# CAN-Sheet.net
KiCad netlist of a schematic drawn in Altium Designer
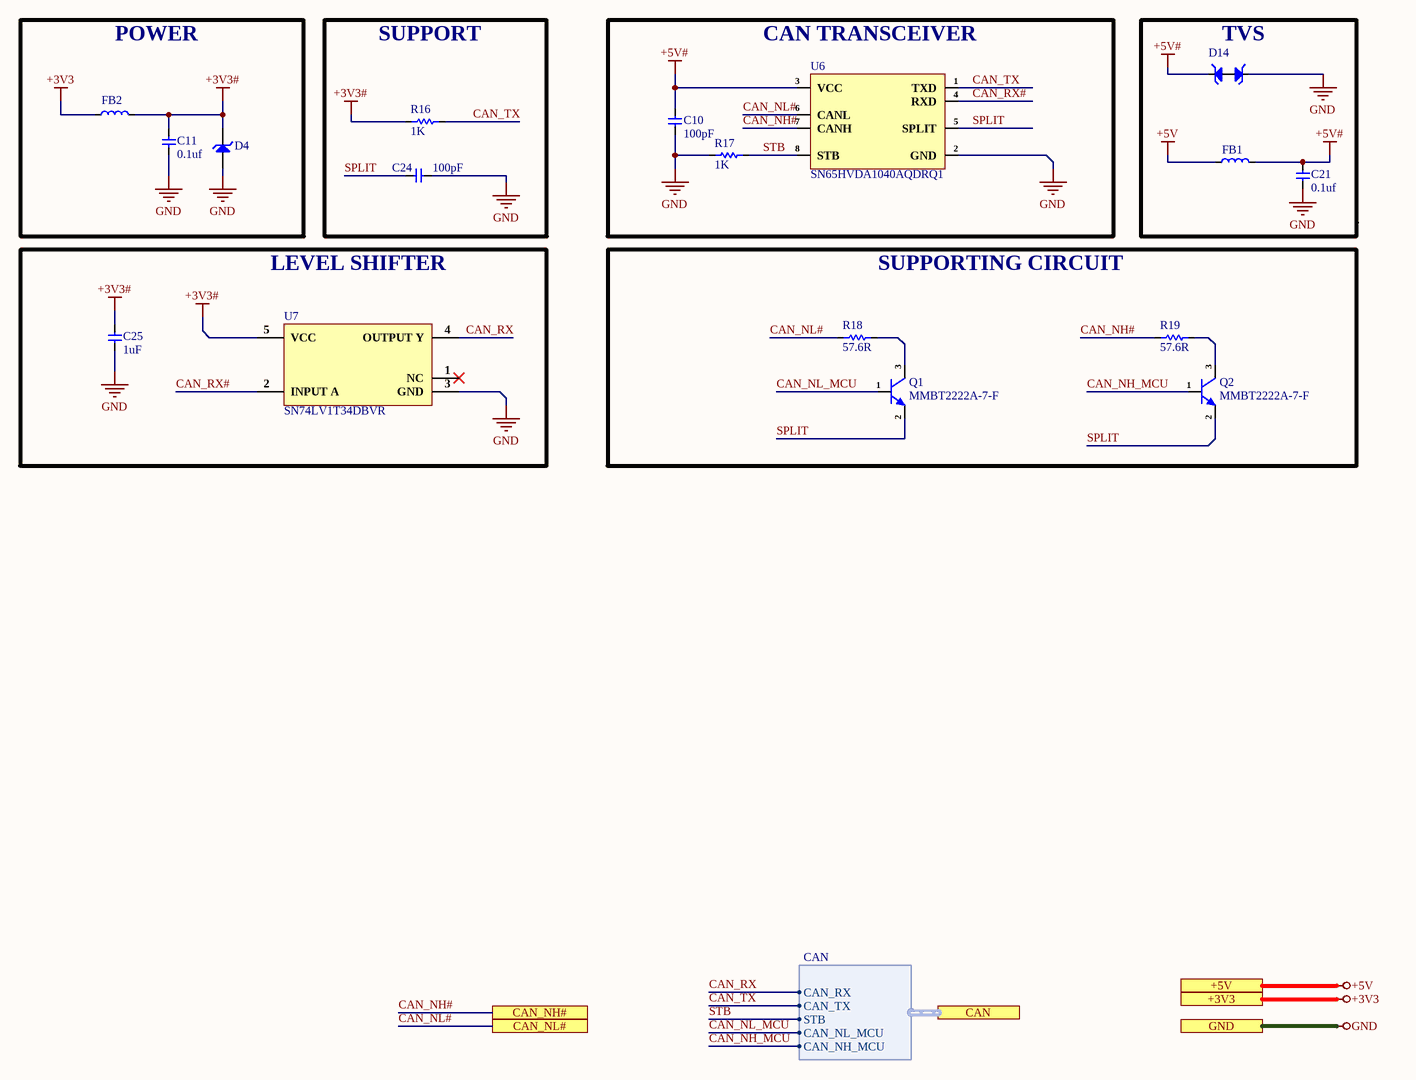
[diagram p0: CAN-Sheet.SchDoc]

(export (version "E")
  (design (tool "Eeschema 10.0.6"))
  (components
    (comp (ref "C10")
      (value "100pF")
      (footprint "Cap-0402")
      (description "CAP CER 100PF 50V C0G/NPO 0402")
      (fields
        (field (name "MANUFACTURER") "Yageo")
        (field (name "MANUFACTURER PART NUMBER") "CC0402JRNPO9BN101")
      )
      (libsource (lib "eSpark Libraries") (part "CC0402JRNPO9BN101"))
    )
    (comp (ref "C11")
      (value "0.1uf")
      (footprint "Cap-0402")
      (description "CAP CER 0.1UF 100V X5R 0402")
      (fields
        (field (name "MANUFACTURER") "Murata")
        (field (name "MANUFACTURER PART NUMBER") "GRM155R62A104KE14D")
      )
      (libsource (lib "eSpark Libraries") (part "GRM155R62A104KE14D"))
    )
    (comp (ref "C21")
      (value "0.1uf")
      (footprint "Cap-0402")
      (description "CAP CER 0.1UF 100V X5R 0402")
      (fields
        (field (name "MANUFACTURER") "Murata")
        (field (name "MANUFACTURER PART NUMBER") "GRM155R62A104KE14D")
      )
      (libsource (lib "eSpark Libraries") (part "GRM155R62A104KE14D"))
    )
    (comp (ref "C24")
      (value "100pF")
      (footprint "Cap-0402")
      (description "CAP CER 100PF 50V C0G/NPO 0402")
      (fields
        (field (name "MANUFACTURER") "Yageo")
        (field (name "MANUFACTURER PART NUMBER") "CC0402JRNPO9BN101")
      )
      (libsource (lib "eSpark Libraries") (part "CC0402JRNPO9BN101"))
    )
    (comp (ref "C25")
      (value "1uF")
      (footprint "Cap-0603")
      (description "CAP CER 1UF 25V X5R 0603")
      (fields
        (field (name "MANUFACTURER") "Yageo")
        (field (name "MANUFACTURER PART NUMBER") "CC0603KRX5R8BB105")
      )
      (libsource (lib "eSpark Libraries") (part "CC0603KRX5R8BB105"))
    )
    (comp (ref "D4")
      (value "AZ3003-01G")
      (footprint "SOD-123")
      (description "TVS SURGE PROTECTOR 1-CH 3.3V")
      (fields (field (name "MANUFACTURER") "Amazing"))
      (libsource (lib "eSpark Libraries") (part "AZ3003-01G"))
    )
    (comp (ref "D14")
      (value "PESD5V0H1BSFYL")
      (footprint "DSN0603-2")
      (description "TVS DIODE 5VWM 6.3VC DSN0603-2")
      (fields (field (name "MANUFACTURER") "Nexperia") (field (name "LCSC PART NUMBER") "C477989"))
      (libsource (lib "eSpark Libraries") (part "PESD5V0H1BSFYL"))
    )
    (comp (ref "FB1")
      (value "MPZ1608S121ATDH5")
      (footprint "IND-0603 (1608 Metric)")
      (description "FERRITE BEAD 120 OHM 0603 1LN")
      (fields (field (name "MANUFACTURER") "TDK") (field (name "TOLERANCE") "25%"))
      (libsource (lib "eSpark Libraries") (part "MPZ1608S121ATDH5"))
    )
    (comp (ref "FB2")
      (value "BLM15PG100SN1D")
      (footprint "IND-0402")
      (description "FERRITE BEAD 10 OHM 0402 1LN")
      (fields (field (name "MANUFACTURER") "Murata") (field (name "TOLERANCE") "25%"))
      (libsource (lib "eSpark Libraries") (part "BLM15PG100SN1D"))
    )
    (comp (ref "Q1")
      (value "MMBT2222A-7-F")
      (footprint "SOT-23")
      (description "TRANS NPN 40V 0.6A SMD SOT23-3")
      (fields (field (name "MANUFACTURER") "Diodes") (field (name "VOLTAGE") "40V"))
      (libsource (lib "eSpark Libraries") (part "MMBT2222A-7-F"))
    )
    (comp (ref "Q2")
      (value "MMBT2222A-7-F")
      (footprint "SOT-23")
      (description "TRANS NPN 40V 0.6A SMD SOT23-3")
      (fields (field (name "MANUFACTURER") "Diodes") (field (name "VOLTAGE") "40V"))
      (libsource (lib "eSpark Libraries") (part "MMBT2222A-7-F"))
    )
    (comp (ref "R16")
      (value "1K")
      (footprint "Res-0402")
      (description "RES 1K OHM 1% 1/16W 0402")
      (fields
        (field (name "MANUFACTURER") "Yageo")
        (field (name "MANUFACTURER PART NUMBER") "RC0402FR-071KL")
      )
      (libsource (lib "eSpark Libraries") (part "RC0402FR-071KL"))
    )
    (comp (ref "R17")
      (value "1K")
      (footprint "Res-0402")
      (description "RES SMD 1K OHM 1% 1/5W 0402")
      (fields
        (field (name "MANUFACTURER") "Vishay Dale")
        (field (name "MANUFACTURER PART NUMBER") "CRCW04021K00FKEDHP")
      )
      (libsource (lib "eSpark Libraries") (part "CRCW04021K00FKEDHP"))
    )
    (comp (ref "R18")
      (value "57.6R")
      (footprint "Res-0402")
      (description "RES SMD 57.6 OHM 1% 1/10W 0402")
      (fields
        (field (name "MANUFACTURER") "Panasonic")
        (field (name "MANUFACTURER PART NUMBER") "ERJ-2RKF57R6X")
      )
      (libsource (lib "eSpark Libraries") (part "ERJ-2RKF57R6X"))
    )
    (comp (ref "R19")
      (value "57.6R")
      (footprint "Res-0402")
      (description "RES SMD 57.6 OHM 1% 1/10W 0402")
      (fields
        (field (name "MANUFACTURER") "Panasonic")
        (field (name "MANUFACTURER PART NUMBER") "ERJ-2RKF57R6X")
      )
      (libsource (lib "eSpark Libraries") (part "ERJ-2RKF57R6X"))
    )
    (comp (ref "U6")
      (value "SN65HVDA1040AQDRQ1")
      (footprint "SOIC-8(0.154\", 3.90mm Width)")
      (description "IC TRANSCEIVER HALF 1/1 8SOIC")
      (fields (field (name "LCSC PART NUMBER") "C188675") (field (name "MANUFACTURER") "Texas Instruments"))
      (libsource (lib "eSpark Libraries") (part "SN65HVDA1040AQDRQ1"))
    )
    (comp (ref "U7")
      (value "SN74LV1T34DBVR")
      (footprint "SOT-23-5")
      (description "IC BUF NON-INVERT 5.5V SOT23-5")
      (fields (field (name "MANUFACTURER") "Texas Instruments") (field (name "LCSC PART NUMBER") "C100024"))
      (libsource (lib "eSpark Libraries") (part "SN74LV1T34DBVR"))
    )
  )
  (nets
    (net (code "2") (name "+3V3") (class "Default")
      (node (ref "FB2") (pin "1") (pinfunction "1_1") (pintype "passive"))
    )
    (net (code "3") (name "+3V3#") (class "Default")
      (node (ref "C11") (pin "2") (pinfunction "2_2") (pintype "passive"))
      (node (ref "C25") (pin "2") (pinfunction "2_2") (pintype "passive"))
      (node (ref "D4") (pin "2") (pinfunction "K_2") (pintype "passive"))
      (node (ref "FB2") (pin "2") (pinfunction "2_2") (pintype "passive"))
      (node (ref "R16") (pin "1") (pinfunction "1_1") (pintype "passive"))
      (node (ref "U7") (pin "5") (pinfunction "VCC_5") (pintype "passive"))
    )
    (net (code "4") (name "+5V") (class "Default")
      (node (ref "FB1") (pin "1") (pinfunction "1_1") (pintype "passive"))
    )
    (net (code "5") (name "+5V#") (class "Default")
      (node (ref "C10") (pin "1") (pinfunction "1_1") (pintype "passive"))
      (node (ref "C21") (pin "2") (pinfunction "2_2") (pintype "passive"))
      (node (ref "D14") (pin "2") (pinfunction "2_2") (pintype "passive"))
      (node (ref "FB1") (pin "2") (pinfunction "2_2") (pintype "passive"))
      (node (ref "U6") (pin "3") (pinfunction "VCC_3") (pintype "passive"))
    )
    (net (code "6") (name "/CAN_NH#") (class "Default")
      (node (ref "R19") (pin "1") (pinfunction "1_1") (pintype "passive"))
      (node (ref "U6") (pin "7") (pinfunction "CANH_7") (pintype "passive"))
    )
    (net (code "7") (name "/CAN_NH_MCU") (class "Default")
      (node (ref "Q2") (pin "1") (pinfunction "B_1") (pintype "passive"))
    )
    (net (code "8") (name "/CAN_NL#") (class "Default")
      (node (ref "R18") (pin "1") (pinfunction "1_1") (pintype "passive"))
      (node (ref "U6") (pin "6") (pinfunction "CANL_6") (pintype "passive"))
    )
    (net (code "9") (name "/CAN_NL_MCU") (class "Default")
      (node (ref "Q1") (pin "1") (pinfunction "B_1") (pintype "passive"))
    )
    (net (code "10") (name "/CAN_RX") (class "Default")
      (node (ref "U7") (pin "4") (pinfunction "OUTPUT_Y_4") (pintype "passive"))
    )
    (net (code "11") (name "/CAN_RX#") (class "Default")
      (node (ref "U6") (pin "4") (pinfunction "RXD_4") (pintype "passive"))
      (node (ref "U7") (pin "2") (pinfunction "INPUT_A_2") (pintype "passive"))
    )
    (net (code "12") (name "/CAN_TX") (class "Default")
      (node (ref "R16") (pin "2") (pinfunction "2_2") (pintype "passive"))
      (node (ref "U6") (pin "1") (pinfunction "TXD_1") (pintype "passive"))
    )
    (net (code "13") (name "/SPLIT") (class "Default")
      (node (ref "C24") (pin "2") (pinfunction "2_2") (pintype "passive"))
      (node (ref "Q1") (pin "2") (pinfunction "E_2") (pintype "passive"))
      (node (ref "Q2") (pin "2") (pinfunction "E_2") (pintype "passive"))
      (node (ref "U6") (pin "5") (pinfunction "SPLIT_5") (pintype "passive"))
    )
    (net (code "14") (name "/STB") (class "Default")
      (node (ref "R17") (pin "2") (pinfunction "2_2") (pintype "passive"))
      (node (ref "U6") (pin "8") (pinfunction "STB_8") (pintype "passive"))
    )
    (net (code "16") (name "GND") (class "Default")
      (node (ref "C10") (pin "2") (pinfunction "2_2") (pintype "passive"))
      (node (ref "C11") (pin "1") (pinfunction "1_1") (pintype "passive"))
      (node (ref "C21") (pin "1") (pinfunction "1_1") (pintype "passive"))
      (node (ref "C24") (pin "1") (pinfunction "1_1") (pintype "passive"))
      (node (ref "C25") (pin "1") (pinfunction "1_1") (pintype "passive"))
      (node (ref "D14") (pin "1") (pinfunction "1_1") (pintype "passive"))
      (node (ref "D4") (pin "1") (pinfunction "A_1") (pintype "passive"))
      (node (ref "R17") (pin "1") (pinfunction "1_1") (pintype "passive"))
      (node (ref "U6") (pin "2") (pinfunction "GND_2") (pintype "passive"))
      (node (ref "U7") (pin "3") (pinfunction "GND_3") (pintype "passive"))
    )
    (net (code "17") (name "Net-(Q1-C)") (class "Default")
      (node (ref "Q1") (pin "3") (pinfunction "C_3") (pintype "passive"))
      (node (ref "R18") (pin "2") (pinfunction "2_2") (pintype "passive"))
    )
    (net (code "18") (name "Net-(Q2-C)") (class "Default")
      (node (ref "Q2") (pin "3") (pinfunction "C_3") (pintype "passive"))
      (node (ref "R19") (pin "2") (pinfunction "2_2") (pintype "passive"))
    )
    (net (code "19") (name "unconnected-(U7-NC-Pad1)") (class "Default")
      (node (ref "U7") (pin "1") (pinfunction "NC_1") (pintype "passive+no_connect"))
    )
  )
)
